# Sensor-light.net
KiCad netlist of a schematic drawn in EAGLE
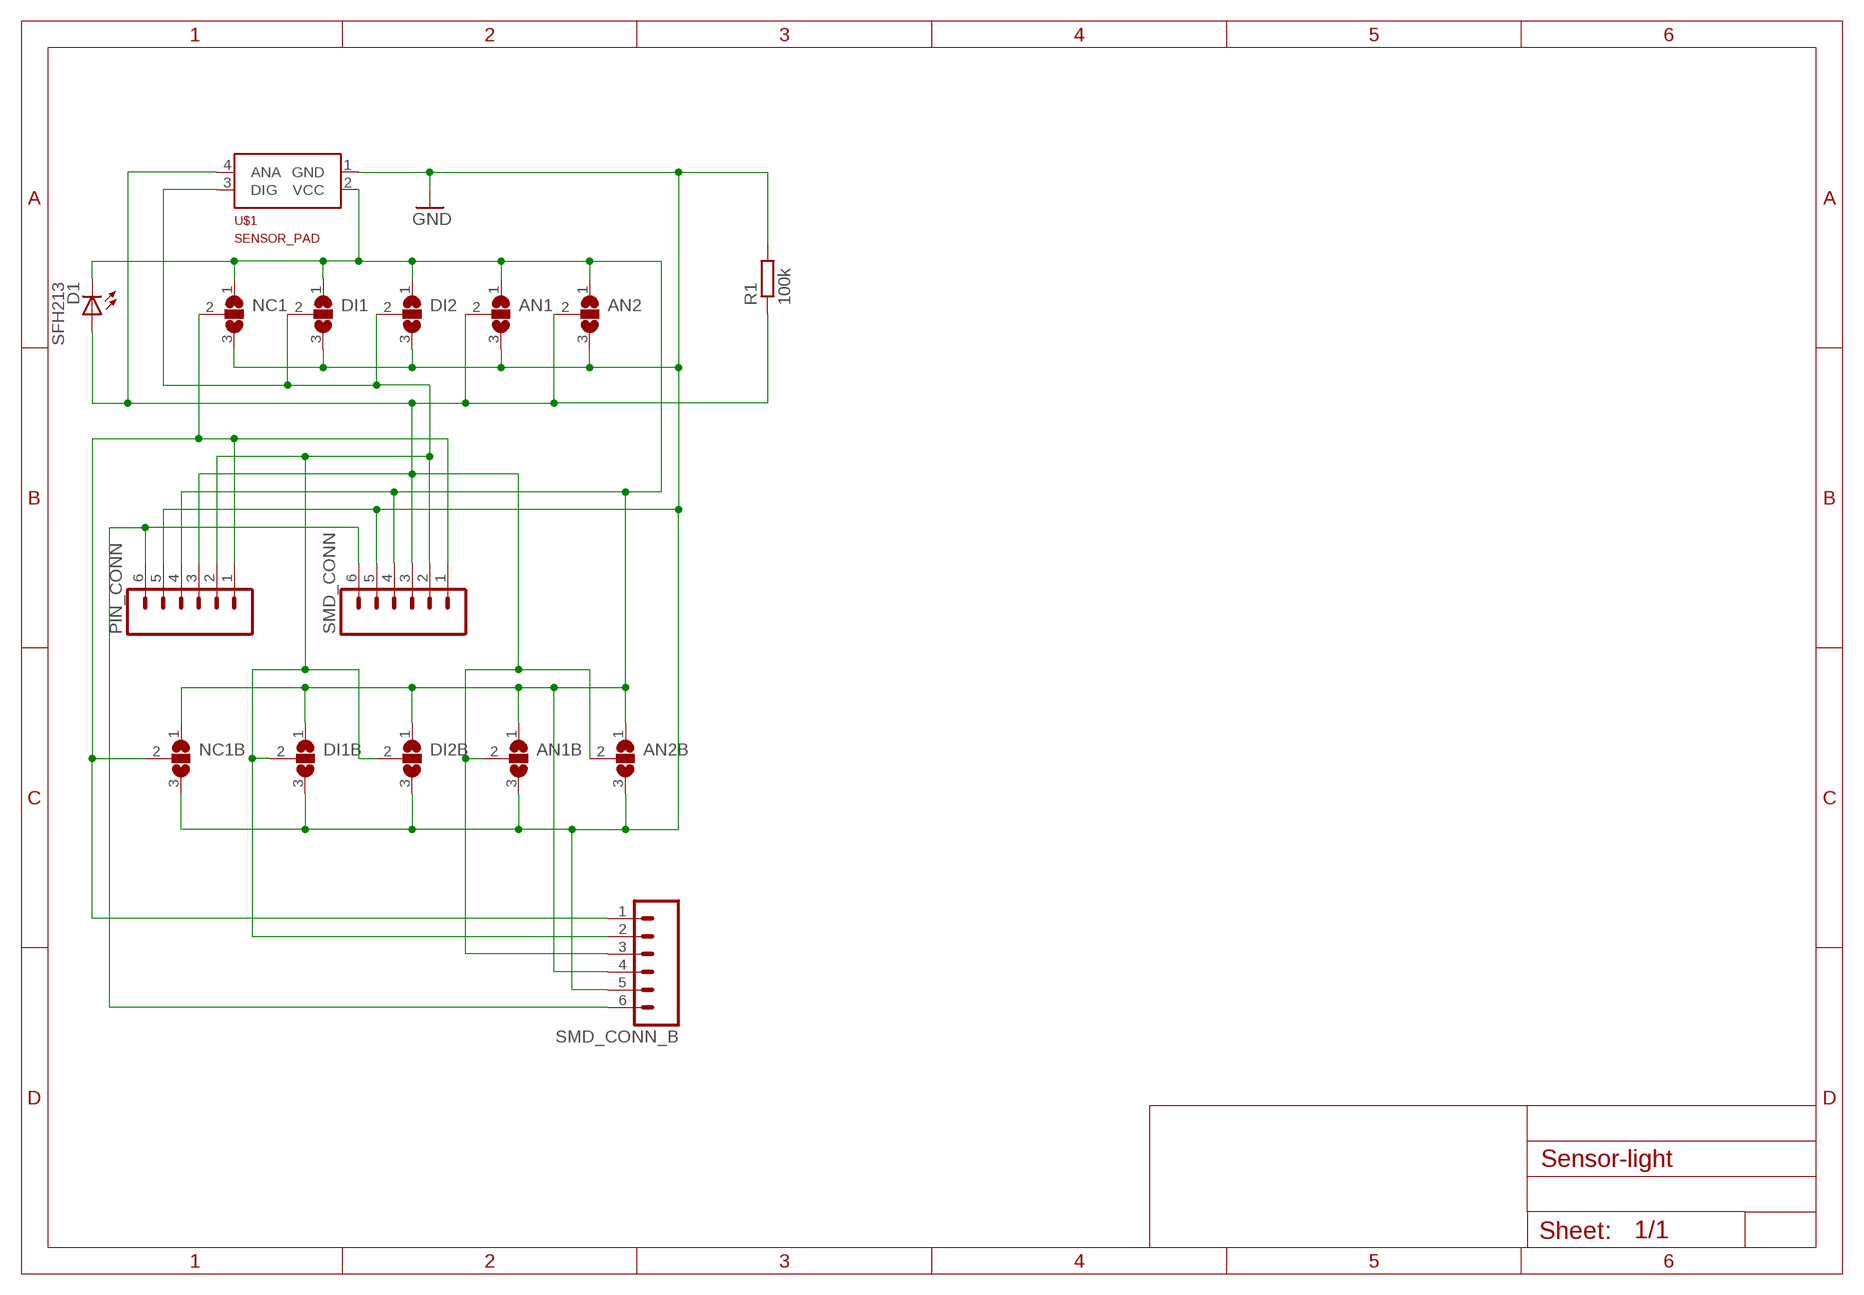
[diagram p0: schematic, sheet 1]

(export (version "E")
  (design (tool "Eeschema 10.0.6"))
  (components
    (comp (ref "AN1")
      (value "SJ2W")
      (footprint "eagle-import:SJ_2")
      (libsource (lib "eagle-import") (part "SJ2W"))
    )
    (comp (ref "AN1B")
      (value "SJ2W")
      (footprint "eagle-import:SJ_2")
      (libsource (lib "eagle-import") (part "SJ2W"))
    )
    (comp (ref "AN2")
      (value "SJ2W")
      (footprint "eagle-import:SJ_2")
      (libsource (lib "eagle-import") (part "SJ2W"))
    )
    (comp (ref "AN2B")
      (value "SJ2W")
      (footprint "eagle-import:SJ_2")
      (libsource (lib "eagle-import") (part "SJ2W"))
    )
    (comp (ref "D1")
      (value "SFH213")
      (footprint "eagle-import:LED5MM")
      (fields (field (name "MF") "OSRAM"))
      (libsource (lib "eagle-import") (part "LED5MM"))
    )
    (comp (ref "DI1")
      (value "SJ2W")
      (footprint "eagle-import:SJ_2")
      (libsource (lib "eagle-import") (part "SJ2W"))
    )
    (comp (ref "DI1B")
      (value "SJ2W")
      (footprint "eagle-import:SJ_2")
      (libsource (lib "eagle-import") (part "SJ2W"))
    )
    (comp (ref "DI2")
      (value "SJ2W")
      (footprint "eagle-import:SJ_2")
      (libsource (lib "eagle-import") (part "SJ2W"))
    )
    (comp (ref "DI2B")
      (value "SJ2W")
      (footprint "eagle-import:SJ_2")
      (libsource (lib "eagle-import") (part "SJ2W"))
    )
    (comp (ref "NC1")
      (value "SJ2W")
      (footprint "eagle-import:SJ_2")
      (libsource (lib "eagle-import") (part "SJ2W"))
    )
    (comp (ref "NC1B")
      (value "SJ2W")
      (footprint "eagle-import:SJ_2")
      (libsource (lib "eagle-import") (part "SJ2W"))
    )
    (comp (ref "PIN_CONN")
      (value "M06SILK_FEMALE_PTH")
      (footprint "eagle-import:1X06")
      (libsource (lib "eagle-import") (part "M06SILK_FEMALE_PTH"))
    )
    (comp (ref "R1")
      (value "100k")
      (footprint "eagle-import:R0805_SMALL")
      (fields (field (name "MF") "VISHAY DRALORIC") (field (name "MPN") "CRCW0805100KFKEA"))
      (libsource (lib "eagle-import") (part "R0805_SMALL"))
    )
    (comp (ref "SMD_CONN")
      (value "M06SMD-STRAIGHT-COMBO-FEMALE")
      (footprint "eagle-import:1X06_SMD_STRAIGHT_COMBO")
      (libsource (lib "eagle-import") (part "M06SMD-STRAIGHT-COMBO-FEMALE"))
    )
    (comp (ref "SMD_CONN_B")
      (value "M06SMD-STRAIGHT-COMBO-FEMALE")
      (footprint "eagle-import:1X06_SMD_STRAIGHT_COMBO")
      (libsource (lib "eagle-import") (part "M06SMD-STRAIGHT-COMBO-FEMALE"))
    )
    (comp (ref "U$1")
      (value "SENSOR_PAD")
      (footprint "eagle-import:SENSOR_PAD")
      (libsource (lib "eagle-import") (part "SENSOR_PAD"))
    )
  )
  (nets
    (net (code "1") (name "GND") (class "Default")
      (node (ref "AN1") (pin "3") (pinfunction "3_3") (pintype "passive"))
      (node (ref "AN1B") (pin "3") (pinfunction "3_3") (pintype "passive"))
      (node (ref "AN2") (pin "3") (pinfunction "3_3") (pintype "passive"))
      (node (ref "AN2B") (pin "3") (pinfunction "3_3") (pintype "passive"))
      (node (ref "DI1") (pin "3") (pinfunction "3_3") (pintype "passive"))
      (node (ref "DI1B") (pin "3") (pinfunction "3_3") (pintype "passive"))
      (node (ref "DI2") (pin "3") (pinfunction "3_3") (pintype "passive"))
      (node (ref "DI2B") (pin "3") (pinfunction "3_3") (pintype "passive"))
      (node (ref "NC1") (pin "3") (pinfunction "3_3") (pintype "passive"))
      (node (ref "NC1B") (pin "3") (pinfunction "3_3") (pintype "passive"))
      (node (ref "PIN_CONN") (pin "5") (pinfunction "5_5") (pintype "passive"))
      (node (ref "R1") (pin "2") (pinfunction "2_2") (pintype "passive"))
      (node (ref "SMD_CONN") (pin "5") (pinfunction "5_5") (pintype "passive"))
      (node (ref "SMD_CONN_B") (pin "5") (pinfunction "5_5") (pintype "passive"))
      (node (ref "U$1") (pin "1") (pinfunction "GND_1") (pintype "bidirectional"))
    )
    (net (code "2") (name "Net-(D1-C)") (class "Default")
      (node (ref "AN1") (pin "1") (pinfunction "1_1") (pintype "passive"))
      (node (ref "AN1B") (pin "1") (pinfunction "1_1") (pintype "passive"))
      (node (ref "AN2") (pin "1") (pinfunction "1_1") (pintype "passive"))
      (node (ref "AN2B") (pin "1") (pinfunction "1_1") (pintype "passive"))
      (node (ref "D1") (pin "K") (pinfunction "C_K") (pintype "passive"))
      (node (ref "DI1") (pin "1") (pinfunction "1_1") (pintype "passive"))
      (node (ref "DI1B") (pin "1") (pinfunction "1_1") (pintype "passive"))
      (node (ref "DI2") (pin "1") (pinfunction "1_1") (pintype "passive"))
      (node (ref "DI2B") (pin "1") (pinfunction "1_1") (pintype "passive"))
      (node (ref "NC1") (pin "1") (pinfunction "1_1") (pintype "passive"))
      (node (ref "NC1B") (pin "1") (pinfunction "1_1") (pintype "passive"))
      (node (ref "PIN_CONN") (pin "4") (pinfunction "4_4") (pintype "passive"))
      (node (ref "SMD_CONN") (pin "4") (pinfunction "4_4") (pintype "passive"))
      (node (ref "SMD_CONN_B") (pin "4") (pinfunction "4_4") (pintype "passive"))
      (node (ref "U$1") (pin "2") (pinfunction "VCC_2") (pintype "bidirectional"))
    )
    (net (code "3") (name "Net-(NC1-Pad2)") (class "Default")
      (node (ref "NC1") (pin "2") (pinfunction "2_2") (pintype "passive"))
      (node (ref "NC1B") (pin "2") (pinfunction "2_2") (pintype "passive"))
      (node (ref "PIN_CONN") (pin "1") (pinfunction "1_1") (pintype "passive"))
      (node (ref "SMD_CONN") (pin "1") (pinfunction "1_1") (pintype "passive"))
      (node (ref "SMD_CONN_B") (pin "1") (pinfunction "1_1") (pintype "passive"))
    )
    (net (code "4") (name "Net-(PIN_CONN-Pad6)") (class "Default")
      (node (ref "PIN_CONN") (pin "6") (pinfunction "6_6") (pintype "passive"))
      (node (ref "SMD_CONN") (pin "6") (pinfunction "6_6") (pintype "passive"))
      (node (ref "SMD_CONN_B") (pin "6") (pinfunction "6_6") (pintype "passive"))
    )
    (net (code "5") (name "Net-(U$1-ANA)") (class "Default")
      (node (ref "AN1") (pin "2") (pinfunction "2_2") (pintype "passive"))
      (node (ref "AN1B") (pin "2") (pinfunction "2_2") (pintype "passive"))
      (node (ref "AN2") (pin "2") (pinfunction "2_2") (pintype "passive"))
      (node (ref "AN2B") (pin "2") (pinfunction "2_2") (pintype "passive"))
      (node (ref "D1") (pin "A") (pinfunction "A_A") (pintype "passive"))
      (node (ref "PIN_CONN") (pin "3") (pinfunction "3_3") (pintype "passive"))
      (node (ref "R1") (pin "1") (pinfunction "1_1") (pintype "passive"))
      (node (ref "SMD_CONN") (pin "3") (pinfunction "3_3") (pintype "passive"))
      (node (ref "SMD_CONN_B") (pin "3") (pinfunction "3_3") (pintype "passive"))
      (node (ref "U$1") (pin "4") (pinfunction "ANA_4") (pintype "bidirectional"))
    )
    (net (code "6") (name "Net-(U$1-DIG)") (class "Default")
      (node (ref "DI1") (pin "2") (pinfunction "2_2") (pintype "passive"))
      (node (ref "DI1B") (pin "2") (pinfunction "2_2") (pintype "passive"))
      (node (ref "DI2") (pin "2") (pinfunction "2_2") (pintype "passive"))
      (node (ref "DI2B") (pin "2") (pinfunction "2_2") (pintype "passive"))
      (node (ref "PIN_CONN") (pin "2") (pinfunction "2_2") (pintype "passive"))
      (node (ref "SMD_CONN") (pin "2") (pinfunction "2_2") (pintype "passive"))
      (node (ref "SMD_CONN_B") (pin "2") (pinfunction "2_2") (pintype "passive"))
      (node (ref "U$1") (pin "3") (pinfunction "DIG_3") (pintype "bidirectional"))
    )
  )
)
